# DIGITAL_INPUT.net
KiCad netlist of a schematic drawn in Altium Designer
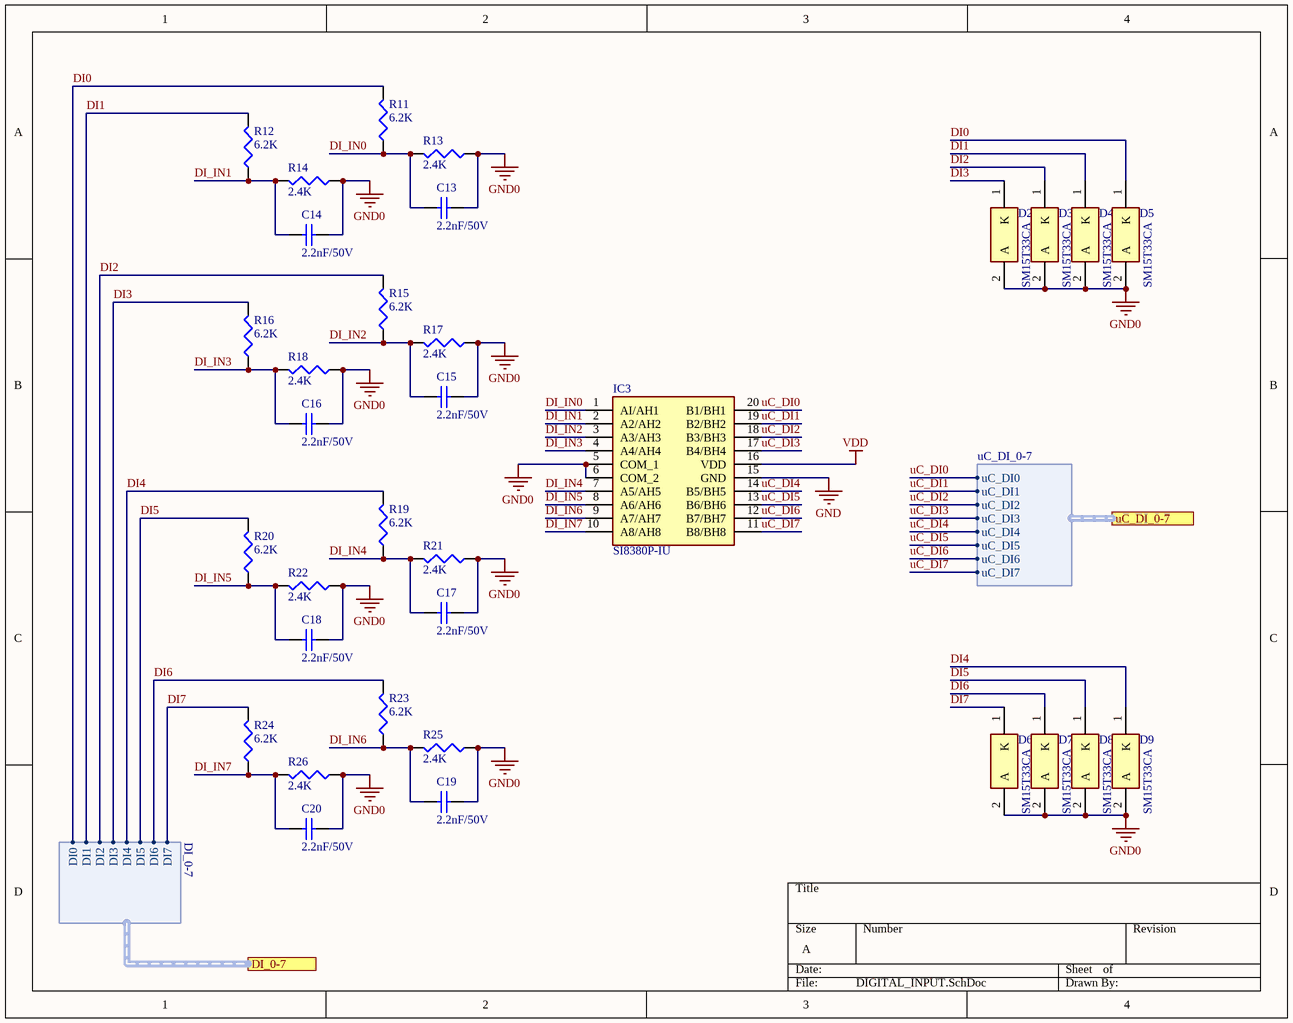
[diagram p0: DIGITAL_INPUT.SchDoc]

(export (version "E")
  (design (tool "Eeschema 10.0.6"))
  (components
    (comp (ref "C13")
      (value "2.2nF/50V")
      (footprint "C1210")
      (description "Capacitor (Semiconductor SIM Model)")
      (fields (field (name "PUBLISHER") "Altium Limited"))
      (libsource (lib "Miscellaneous Devices") (part "Cap Semi"))
    )
    (comp (ref "C14")
      (value "2.2nF/50V")
      (footprint "C1210")
      (description "Capacitor (Semiconductor SIM Model)")
      (fields (field (name "PUBLISHER") "Altium Limited"))
      (libsource (lib "Miscellaneous Devices") (part "Cap Semi"))
    )
    (comp (ref "C15")
      (value "2.2nF/50V")
      (footprint "C1210")
      (description "Capacitor (Semiconductor SIM Model)")
      (fields (field (name "PUBLISHER") "Altium Limited"))
      (libsource (lib "Miscellaneous Devices") (part "Cap Semi"))
    )
    (comp (ref "C16")
      (value "2.2nF/50V")
      (footprint "C1210")
      (description "Capacitor (Semiconductor SIM Model)")
      (fields (field (name "PUBLISHER") "Altium Limited"))
      (libsource (lib "Miscellaneous Devices") (part "Cap Semi"))
    )
    (comp (ref "C17")
      (value "2.2nF/50V")
      (footprint "C1210")
      (description "Capacitor (Semiconductor SIM Model)")
      (fields (field (name "PUBLISHER") "Altium Limited"))
      (libsource (lib "Miscellaneous Devices") (part "Cap Semi"))
    )
    (comp (ref "C18")
      (value "2.2nF/50V")
      (footprint "C1210")
      (description "Capacitor (Semiconductor SIM Model)")
      (fields (field (name "PUBLISHER") "Altium Limited"))
      (libsource (lib "Miscellaneous Devices") (part "Cap Semi"))
    )
    (comp (ref "C19")
      (value "2.2nF/50V")
      (footprint "C1210")
      (description "Capacitor (Semiconductor SIM Model)")
      (fields (field (name "PUBLISHER") "Altium Limited"))
      (libsource (lib "Miscellaneous Devices") (part "Cap Semi"))
    )
    (comp (ref "C20")
      (value "2.2nF/50V")
      (footprint "C1210")
      (description "Capacitor (Semiconductor SIM Model)")
      (fields (field (name "PUBLISHER") "Altium Limited"))
      (libsource (lib "Miscellaneous Devices") (part "Cap Semi"))
    )
    (comp (ref "D2")
      (value "SM15T33CA")
      (footprint "DIONM8059X265N")
      (description "Diode")
      (fields (field (name "MOUSER PART NUMBER") "511-SM15T33CA") (field (name "RS PART NUMBER") "9196428"))
      (libsource (lib "BV100011_UniversalSlave") (part "SM15T33CA"))
    )
    (comp (ref "D3")
      (value "SM15T33CA")
      (footprint "DIONM8059X265N")
      (description "Diode")
      (fields (field (name "MOUSER PART NUMBER") "511-SM15T33CA") (field (name "RS PART NUMBER") "9196428"))
      (libsource (lib "BV100011_UniversalSlave") (part "SM15T33CA"))
    )
    (comp (ref "D4")
      (value "SM15T33CA")
      (footprint "DIONM8059X265N")
      (description "Diode")
      (fields (field (name "MOUSER PART NUMBER") "511-SM15T33CA") (field (name "RS PART NUMBER") "9196428"))
      (libsource (lib "BV100011_UniversalSlave") (part "SM15T33CA"))
    )
    (comp (ref "D5")
      (value "SM15T33CA")
      (footprint "DIONM8059X265N")
      (description "Diode")
      (fields (field (name "MOUSER PART NUMBER") "511-SM15T33CA") (field (name "RS PART NUMBER") "9196428"))
      (libsource (lib "BV100011_UniversalSlave") (part "SM15T33CA"))
    )
    (comp (ref "D6")
      (value "SM15T33CA")
      (footprint "DIONM8059X265N")
      (description "Diode")
      (fields (field (name "MOUSER PART NUMBER") "511-SM15T33CA") (field (name "RS PART NUMBER") "9196428"))
      (libsource (lib "BV100011_UniversalSlave") (part "SM15T33CA"))
    )
    (comp (ref "D7")
      (value "SM15T33CA")
      (footprint "DIONM8059X265N")
      (description "Diode")
      (fields (field (name "MOUSER PART NUMBER") "511-SM15T33CA") (field (name "RS PART NUMBER") "9196428"))
      (libsource (lib "BV100011_UniversalSlave") (part "SM15T33CA"))
    )
    (comp (ref "D8")
      (value "SM15T33CA")
      (footprint "DIONM8059X265N")
      (description "Diode")
      (fields (field (name "MOUSER PART NUMBER") "511-SM15T33CA") (field (name "RS PART NUMBER") "9196428"))
      (libsource (lib "BV100011_UniversalSlave") (part "SM15T33CA"))
    )
    (comp (ref "D9")
      (value "SM15T33CA")
      (footprint "DIONM8059X265N")
      (description "Diode")
      (fields (field (name "MOUSER PART NUMBER") "511-SM15T33CA") (field (name "RS PART NUMBER") "9196428"))
      (libsource (lib "BV100011_UniversalSlave") (part "SM15T33CA"))
    )
    (comp (ref "IC3")
      (value "SI8380P-IU")
      (footprint "SOP64P600X175-20N")
      (description "Integrated Circuit")
      (fields (field (name "MOUSER PART NUMBER") "634-SI8380P-IU"))
      (libsource (lib "BV100011_UniversalSlave") (part "SI8380P-IU"))
    )
    (comp (ref "R11")
      (value "6.2K")
      (footprint "12Z-2010")
      (description "Resistor")
      (fields (field (name "PUBLISHER") "Altium Limited"))
      (libsource (lib "Miscellaneous Devices") (part "Res3"))
    )
    (comp (ref "R12")
      (value "6.2K")
      (footprint "12Z-2010")
      (description "Resistor")
      (fields (field (name "PUBLISHER") "Altium Limited"))
      (libsource (lib "Miscellaneous Devices") (part "Res3"))
    )
    (comp (ref "R13")
      (value "2.4K")
      (footprint "12Z-2010")
      (description "Resistor")
      (fields (field (name "PUBLISHER") "Altium Limited"))
      (libsource (lib "Miscellaneous Devices") (part "Res3"))
    )
    (comp (ref "R14")
      (value "2.4K")
      (footprint "12Z-2010")
      (description "Resistor")
      (fields (field (name "PUBLISHER") "Altium Limited"))
      (libsource (lib "Miscellaneous Devices") (part "Res3"))
    )
    (comp (ref "R15")
      (value "6.2K")
      (footprint "12Z-2010")
      (description "Resistor")
      (fields (field (name "PUBLISHER") "Altium Limited"))
      (libsource (lib "Miscellaneous Devices") (part "Res3"))
    )
    (comp (ref "R16")
      (value "6.2K")
      (footprint "12Z-2010")
      (description "Resistor")
      (fields (field (name "PUBLISHER") "Altium Limited"))
      (libsource (lib "Miscellaneous Devices") (part "Res3"))
    )
    (comp (ref "R17")
      (value "2.4K")
      (footprint "12Z-2010")
      (description "Resistor")
      (fields (field (name "PUBLISHER") "Altium Limited"))
      (libsource (lib "Miscellaneous Devices") (part "Res3"))
    )
    (comp (ref "R18")
      (value "2.4K")
      (footprint "12Z-2010")
      (description "Resistor")
      (fields (field (name "PUBLISHER") "Altium Limited"))
      (libsource (lib "Miscellaneous Devices") (part "Res3"))
    )
    (comp (ref "R19")
      (value "6.2K")
      (footprint "12Z-2010")
      (description "Resistor")
      (fields (field (name "PUBLISHER") "Altium Limited"))
      (libsource (lib "Miscellaneous Devices") (part "Res3"))
    )
    (comp (ref "R20")
      (value "6.2K")
      (footprint "12Z-2010")
      (description "Resistor")
      (fields (field (name "PUBLISHER") "Altium Limited"))
      (libsource (lib "Miscellaneous Devices") (part "Res3"))
    )
    (comp (ref "R21")
      (value "2.4K")
      (footprint "12Z-2010")
      (description "Resistor")
      (fields (field (name "PUBLISHER") "Altium Limited"))
      (libsource (lib "Miscellaneous Devices") (part "Res3"))
    )
    (comp (ref "R22")
      (value "2.4K")
      (footprint "12Z-2010")
      (description "Resistor")
      (fields (field (name "PUBLISHER") "Altium Limited"))
      (libsource (lib "Miscellaneous Devices") (part "Res3"))
    )
    (comp (ref "R23")
      (value "6.2K")
      (footprint "12Z-2010")
      (description "Resistor")
      (fields (field (name "PUBLISHER") "Altium Limited"))
      (libsource (lib "Miscellaneous Devices") (part "Res3"))
    )
    (comp (ref "R24")
      (value "6.2K")
      (footprint "12Z-2010")
      (description "Resistor")
      (fields (field (name "PUBLISHER") "Altium Limited"))
      (libsource (lib "Miscellaneous Devices") (part "Res3"))
    )
    (comp (ref "R25")
      (value "2.4K")
      (footprint "12Z-2010")
      (description "Resistor")
      (fields (field (name "PUBLISHER") "Altium Limited"))
      (libsource (lib "Miscellaneous Devices") (part "Res3"))
    )
    (comp (ref "R26")
      (value "2.4K")
      (footprint "12Z-2010")
      (description "Resistor")
      (fields (field (name "PUBLISHER") "Altium Limited"))
      (libsource (lib "Miscellaneous Devices") (part "Res3"))
    )
  )
  (nets
    (net (code "3") (name "/DI0") (class "Default")
      (node (ref "D5") (pin "1") (pinfunction "K_1") (pintype "passive"))
      (node (ref "R11") (pin "2") (pinfunction "2_2") (pintype "passive"))
    )
    (net (code "4") (name "/DI1") (class "Default")
      (node (ref "D4") (pin "1") (pinfunction "K_1") (pintype "passive"))
      (node (ref "R12") (pin "2") (pinfunction "2_2") (pintype "passive"))
    )
    (net (code "5") (name "/DI2") (class "Default")
      (node (ref "D3") (pin "1") (pinfunction "K_1") (pintype "passive"))
      (node (ref "R15") (pin "2") (pinfunction "2_2") (pintype "passive"))
    )
    (net (code "6") (name "/DI3") (class "Default")
      (node (ref "D2") (pin "1") (pinfunction "K_1") (pintype "passive"))
      (node (ref "R16") (pin "2") (pinfunction "2_2") (pintype "passive"))
    )
    (net (code "7") (name "/DI4") (class "Default")
      (node (ref "D9") (pin "1") (pinfunction "K_1") (pintype "passive"))
      (node (ref "R19") (pin "2") (pinfunction "2_2") (pintype "passive"))
    )
    (net (code "8") (name "/DI5") (class "Default")
      (node (ref "D8") (pin "1") (pinfunction "K_1") (pintype "passive"))
      (node (ref "R20") (pin "2") (pinfunction "2_2") (pintype "passive"))
    )
    (net (code "9") (name "/DI6") (class "Default")
      (node (ref "D7") (pin "1") (pinfunction "K_1") (pintype "passive"))
      (node (ref "R23") (pin "2") (pinfunction "2_2") (pintype "passive"))
    )
    (net (code "10") (name "/DI7") (class "Default")
      (node (ref "D6") (pin "1") (pinfunction "K_1") (pintype "passive"))
      (node (ref "R24") (pin "2") (pinfunction "2_2") (pintype "passive"))
    )
    (net (code "11") (name "/DI_IN0") (class "Default")
      (node (ref "C13") (pin "1") (pinfunction "1_1") (pintype "passive"))
      (node (ref "IC3") (pin "1") (pinfunction "AI/AH1_1") (pintype "passive"))
      (node (ref "R11") (pin "1") (pinfunction "1_1") (pintype "passive"))
      (node (ref "R13") (pin "2") (pinfunction "2_2") (pintype "passive"))
    )
    (net (code "12") (name "/DI_IN1") (class "Default")
      (node (ref "C14") (pin "1") (pinfunction "1_1") (pintype "passive"))
      (node (ref "IC3") (pin "2") (pinfunction "A2/AH2_2") (pintype "passive"))
      (node (ref "R12") (pin "1") (pinfunction "1_1") (pintype "passive"))
      (node (ref "R14") (pin "2") (pinfunction "2_2") (pintype "passive"))
    )
    (net (code "13") (name "/DI_IN2") (class "Default")
      (node (ref "C15") (pin "1") (pinfunction "1_1") (pintype "passive"))
      (node (ref "IC3") (pin "3") (pinfunction "A3/AH3_3") (pintype "passive"))
      (node (ref "R15") (pin "1") (pinfunction "1_1") (pintype "passive"))
      (node (ref "R17") (pin "2") (pinfunction "2_2") (pintype "passive"))
    )
    (net (code "14") (name "/DI_IN3") (class "Default")
      (node (ref "C16") (pin "1") (pinfunction "1_1") (pintype "passive"))
      (node (ref "IC3") (pin "4") (pinfunction "A4/AH4_4") (pintype "passive"))
      (node (ref "R16") (pin "1") (pinfunction "1_1") (pintype "passive"))
      (node (ref "R18") (pin "2") (pinfunction "2_2") (pintype "passive"))
    )
    (net (code "15") (name "/DI_IN4") (class "Default")
      (node (ref "C17") (pin "1") (pinfunction "1_1") (pintype "passive"))
      (node (ref "IC3") (pin "7") (pinfunction "A5/AH5_7") (pintype "passive"))
      (node (ref "R19") (pin "1") (pinfunction "1_1") (pintype "passive"))
      (node (ref "R21") (pin "2") (pinfunction "2_2") (pintype "passive"))
    )
    (net (code "16") (name "/DI_IN5") (class "Default")
      (node (ref "C18") (pin "1") (pinfunction "1_1") (pintype "passive"))
      (node (ref "IC3") (pin "8") (pinfunction "A6/AH6_8") (pintype "passive"))
      (node (ref "R20") (pin "1") (pinfunction "1_1") (pintype "passive"))
      (node (ref "R22") (pin "2") (pinfunction "2_2") (pintype "passive"))
    )
    (net (code "17") (name "/DI_IN6") (class "Default")
      (node (ref "C19") (pin "1") (pinfunction "1_1") (pintype "passive"))
      (node (ref "IC3") (pin "9") (pinfunction "A7/AH7_9") (pintype "passive"))
      (node (ref "R23") (pin "1") (pinfunction "1_1") (pintype "passive"))
      (node (ref "R25") (pin "2") (pinfunction "2_2") (pintype "passive"))
    )
    (net (code "18") (name "/DI_IN7") (class "Default")
      (node (ref "C20") (pin "1") (pinfunction "1_1") (pintype "passive"))
      (node (ref "IC3") (pin "10") (pinfunction "A8/AH8_10") (pintype "passive"))
      (node (ref "R24") (pin "1") (pinfunction "1_1") (pintype "passive"))
      (node (ref "R26") (pin "2") (pinfunction "2_2") (pintype "passive"))
    )
    (net (code "19") (name "/uC_DI0") (class "Default")
      (node (ref "IC3") (pin "20") (pinfunction "B1/BH1_20") (pintype "passive"))
    )
    (net (code "20") (name "/uC_DI1") (class "Default")
      (node (ref "IC3") (pin "19") (pinfunction "B2/BH2_19") (pintype "passive"))
    )
    (net (code "21") (name "/uC_DI2") (class "Default")
      (node (ref "IC3") (pin "18") (pinfunction "B3/BH3_18") (pintype "passive"))
    )
    (net (code "22") (name "/uC_DI3") (class "Default")
      (node (ref "IC3") (pin "17") (pinfunction "B4/BH4_17") (pintype "passive"))
    )
    (net (code "23") (name "/uC_DI4") (class "Default")
      (node (ref "IC3") (pin "14") (pinfunction "B5/BH5_14") (pintype "passive"))
    )
    (net (code "24") (name "/uC_DI5") (class "Default")
      (node (ref "IC3") (pin "13") (pinfunction "B6/BH6_13") (pintype "passive"))
    )
    (net (code "25") (name "/uC_DI6") (class "Default")
      (node (ref "IC3") (pin "12") (pinfunction "B7/BH7_12") (pintype "passive"))
    )
    (net (code "26") (name "/uC_DI7") (class "Default")
      (node (ref "IC3") (pin "11") (pinfunction "B8/BH8_11") (pintype "passive"))
    )
    (net (code "29") (name "GND") (class "Default")
      (node (ref "IC3") (pin "15") (pinfunction "GND_15") (pintype "passive"))
    )
    (net (code "30") (name "GND0") (class "Default")
      (node (ref "C13") (pin "2") (pinfunction "2_2") (pintype "passive"))
      (node (ref "C14") (pin "2") (pinfunction "2_2") (pintype "passive"))
      (node (ref "C15") (pin "2") (pinfunction "2_2") (pintype "passive"))
      (node (ref "C16") (pin "2") (pinfunction "2_2") (pintype "passive"))
      (node (ref "C17") (pin "2") (pinfunction "2_2") (pintype "passive"))
      (node (ref "C18") (pin "2") (pinfunction "2_2") (pintype "passive"))
      (node (ref "C19") (pin "2") (pinfunction "2_2") (pintype "passive"))
      (node (ref "C20") (pin "2") (pinfunction "2_2") (pintype "passive"))
      (node (ref "D2") (pin "2") (pinfunction "A_2") (pintype "passive"))
      (node (ref "D3") (pin "2") (pinfunction "A_2") (pintype "passive"))
      (node (ref "D4") (pin "2") (pinfunction "A_2") (pintype "passive"))
      (node (ref "D5") (pin "2") (pinfunction "A_2") (pintype "passive"))
      (node (ref "D6") (pin "2") (pinfunction "A_2") (pintype "passive"))
      (node (ref "D7") (pin "2") (pinfunction "A_2") (pintype "passive"))
      (node (ref "D8") (pin "2") (pinfunction "A_2") (pintype "passive"))
      (node (ref "D9") (pin "2") (pinfunction "A_2") (pintype "passive"))
      (node (ref "IC3") (pin "5") (pinfunction "COM_1_5") (pintype "passive"))
      (node (ref "IC3") (pin "6") (pinfunction "COM_2_6") (pintype "passive"))
      (node (ref "R13") (pin "1") (pinfunction "1_1") (pintype "passive"))
      (node (ref "R14") (pin "1") (pinfunction "1_1") (pintype "passive"))
      (node (ref "R17") (pin "1") (pinfunction "1_1") (pintype "passive"))
      (node (ref "R18") (pin "1") (pinfunction "1_1") (pintype "passive"))
      (node (ref "R21") (pin "1") (pinfunction "1_1") (pintype "passive"))
      (node (ref "R22") (pin "1") (pinfunction "1_1") (pintype "passive"))
      (node (ref "R25") (pin "1") (pinfunction "1_1") (pintype "passive"))
      (node (ref "R26") (pin "1") (pinfunction "1_1") (pintype "passive"))
    )
    (net (code "31") (name "VDD") (class "Default")
      (node (ref "IC3") (pin "16") (pinfunction "VDD_16") (pintype "passive"))
    )
  )
)
